# DM3370_OV9782_3-4.net
KiCad netlist of a schematic drawn in Altium Designer
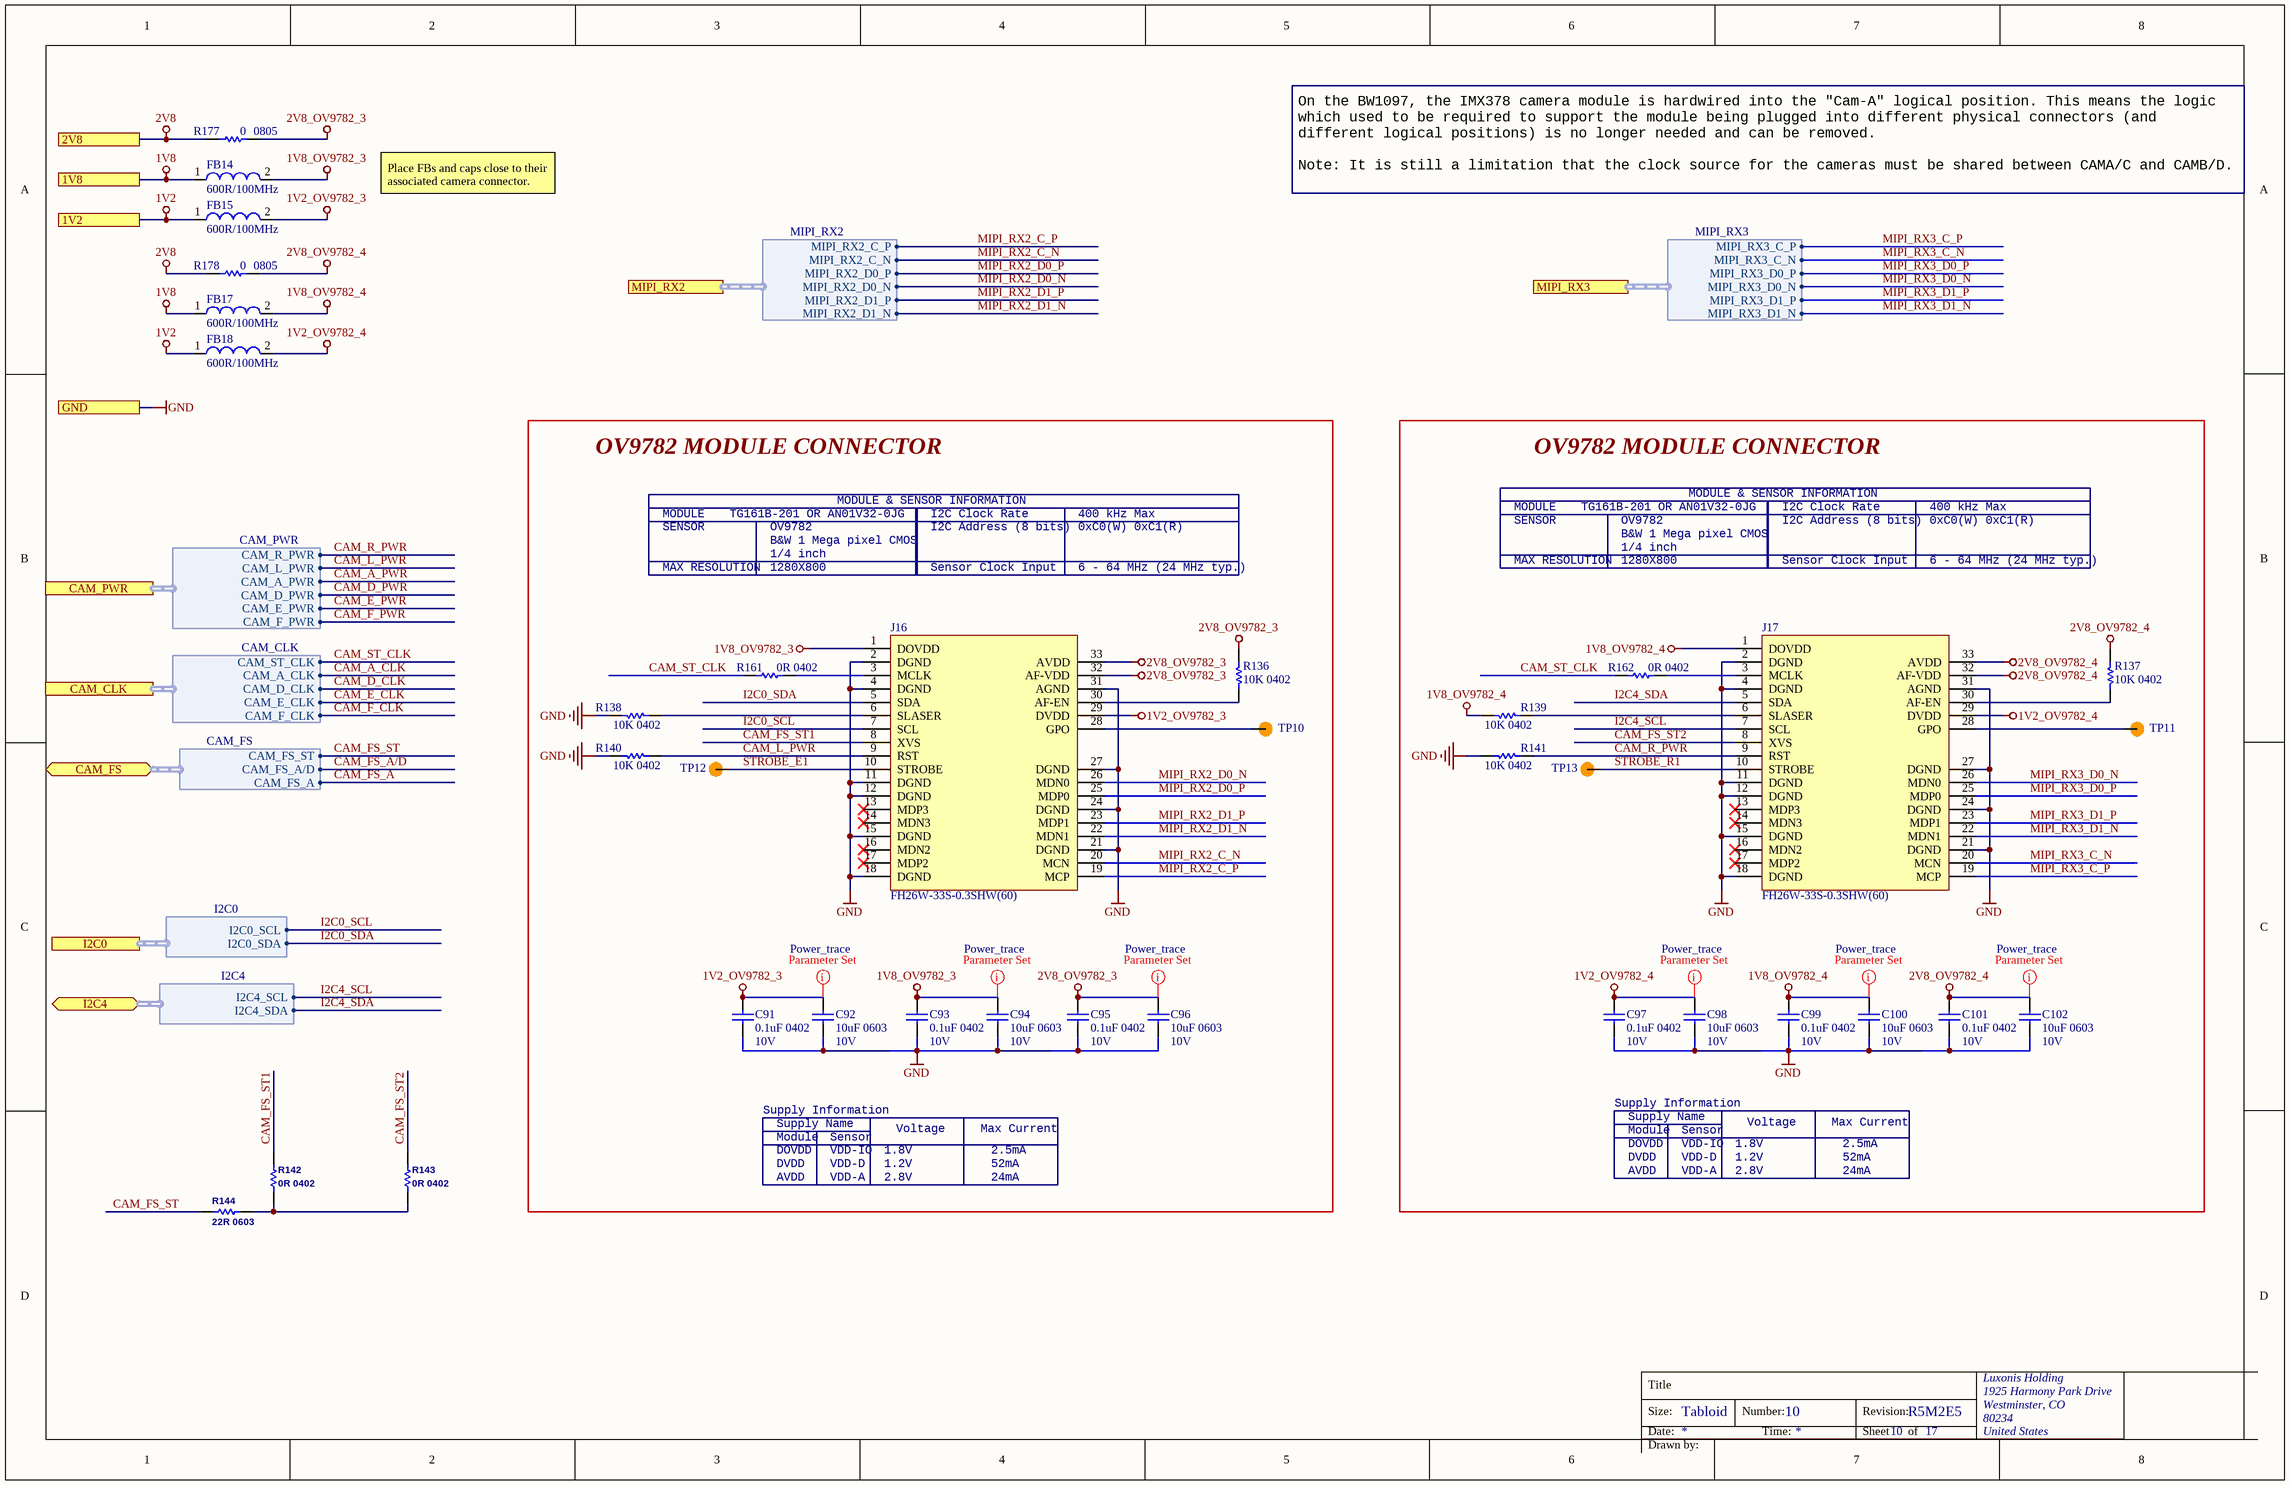
[diagram p0: DM3370_OV9782_3-4.SchDoc]

(export (version "E")
  (design (tool "Eeschema 10.0.6"))
  (components
    (comp (ref "C91")
      (value "0.1uF 0402")
      (footprint "CAP_Altium_Vault_Generic:CAPC0402(1005)70_L")
      (description "CAP CER 0.1UF 10V X7R 0402 5%")
      (fields (field (name "TOLERANCE") "5%") (field (name "VOLTAGE RATING") "10V"))
      (libsource (lib "LuxonisMaster") (part "GRM155R71A104JA01D"))
    )
    (comp (ref "C92")
      (value "10uF 0603")
      (footprint "CAP_Altium_Vault_Generic:CAPC0603(1608)100_L")
      (description "CAP CER 10UF 10V X5R 0603 20%")
      (fields (field (name "TOLERANCE") "20%") (field (name "VOLTAGE RATING") "10V"))
      (libsource (lib "LuxonisMaster") (part "GRM188R61A106ME69D"))
    )
    (comp (ref "C93")
      (value "0.1uF 0402")
      (footprint "CAP_Altium_Vault_Generic:CAPC0402(1005)70_L")
      (description "CAP CER 0.1UF 10V X7R 0402 5%")
      (fields (field (name "TOLERANCE") "5%") (field (name "VOLTAGE RATING") "10V"))
      (libsource (lib "LuxonisMaster") (part "GRM155R71A104JA01D"))
    )
    (comp (ref "C94")
      (value "10uF 0603")
      (footprint "CAP_Altium_Vault_Generic:CAPC0603(1608)100_L")
      (description "CAP CER 10UF 10V X5R 0603 20%")
      (fields (field (name "TOLERANCE") "20%") (field (name "VOLTAGE RATING") "10V"))
      (libsource (lib "LuxonisMaster") (part "GRM188R61A106ME69D"))
    )
    (comp (ref "C95")
      (value "0.1uF 0402")
      (footprint "CAP_Altium_Vault_Generic:CAPC0402(1005)70_L")
      (description "CAP CER 0.1UF 10V X7R 0402 5%")
      (fields (field (name "TOLERANCE") "5%") (field (name "VOLTAGE RATING") "10V"))
      (libsource (lib "LuxonisMaster") (part "GRM155R71A104JA01D"))
    )
    (comp (ref "C96")
      (value "10uF 0603")
      (footprint "CAP_Altium_Vault_Generic:CAPC0603(1608)100_L")
      (description "CAP CER 10UF 10V X5R 0603 20%")
      (fields (field (name "TOLERANCE") "20%") (field (name "VOLTAGE RATING") "10V"))
      (libsource (lib "LuxonisMaster") (part "GRM188R61A106ME69D"))
    )
    (comp (ref "C97")
      (value "0.1uF 0402")
      (footprint "CAP_Altium_Vault_Generic:CAPC0402(1005)70_L")
      (description "CAP CER 0.1UF 10V X7R 0402 5%")
      (fields (field (name "TOLERANCE") "5%") (field (name "VOLTAGE RATING") "10V"))
      (libsource (lib "LuxonisMaster") (part "GRM155R71A104JA01D"))
    )
    (comp (ref "C98")
      (value "10uF 0603")
      (footprint "CAP_Altium_Vault_Generic:CAPC0603(1608)100_L")
      (description "CAP CER 10UF 10V X5R 0603 20%")
      (fields (field (name "TOLERANCE") "20%") (field (name "VOLTAGE RATING") "10V"))
      (libsource (lib "LuxonisMaster") (part "GRM188R61A106ME69D"))
    )
    (comp (ref "C99")
      (value "0.1uF 0402")
      (footprint "CAP_Altium_Vault_Generic:CAPC0402(1005)70_L")
      (description "CAP CER 0.1UF 10V X7R 0402 5%")
      (fields (field (name "TOLERANCE") "5%") (field (name "VOLTAGE RATING") "10V"))
      (libsource (lib "LuxonisMaster") (part "GRM155R71A104JA01D"))
    )
    (comp (ref "C100")
      (value "10uF 0603")
      (footprint "CAP_Altium_Vault_Generic:CAPC0603(1608)100_L")
      (description "CAP CER 10UF 10V X5R 0603 20%")
      (fields (field (name "TOLERANCE") "20%") (field (name "VOLTAGE RATING") "10V"))
      (libsource (lib "LuxonisMaster") (part "GRM188R61A106ME69D"))
    )
    (comp (ref "C101")
      (value "0.1uF 0402")
      (footprint "CAP_Altium_Vault_Generic:CAPC0402(1005)70_L")
      (description "CAP CER 0.1UF 10V X7R 0402 5%")
      (fields (field (name "TOLERANCE") "5%") (field (name "VOLTAGE RATING") "10V"))
      (libsource (lib "LuxonisMaster") (part "GRM155R71A104JA01D"))
    )
    (comp (ref "C102")
      (value "10uF 0603")
      (footprint "CAP_Altium_Vault_Generic:CAPC0603(1608)100_L")
      (description "CAP CER 10UF 10V X5R 0603 20%")
      (fields (field (name "TOLERANCE") "20%") (field (name "VOLTAGE RATING") "10V"))
      (libsource (lib "LuxonisMaster") (part "GRM188R61A106ME69D"))
    )
    (comp (ref "FB14")
      (value "600R/100MHz")
      (footprint "LuxonisMaster:2508056017Y2")
      (description "FERRITE BEAD, 0.1OHM, 2A, 0805, 600R/100MHz")
      (fields (field (name "TOLERANCE") "25%"))
      (libsource (lib "LuxonisMaster") (part "2508056017Y2"))
    )
    (comp (ref "FB15")
      (value "600R/100MHz")
      (footprint "LuxonisMaster:2508056017Y2")
      (description "FERRITE BEAD, 0.1OHM, 2A, 0805, 600R/100MHz")
      (fields (field (name "TOLERANCE") "25%"))
      (libsource (lib "LuxonisMaster") (part "2508056017Y2"))
    )
    (comp (ref "FB17")
      (value "600R/100MHz")
      (footprint "LuxonisMaster:2508056017Y2")
      (description "FERRITE BEAD, 0.1OHM, 2A, 0805, 600R/100MHz")
      (fields (field (name "TOLERANCE") "25%"))
      (libsource (lib "LuxonisMaster") (part "2508056017Y2"))
    )
    (comp (ref "FB18")
      (value "600R/100MHz")
      (footprint "LuxonisMaster:2508056017Y2")
      (description "FERRITE BEAD, 0.1OHM, 2A, 0805, 600R/100MHz")
      (fields (field (name "TOLERANCE") "25%"))
      (libsource (lib "LuxonisMaster") (part "2508056017Y2"))
    )
    (comp (ref "J16")
      (value "FH26W-33S-0.3SHW(60)")
      (footprint "FH26W-33S-0.3SHW(60)")
      (description "FFC/FPC Connector, 33 Contact(s), 1 Row(s), Female, Right Angle, Surface Mount Terminal")
      (libsource (lib "Luxonis LLC") (part "FH26W-33S-0.3SHW(60)"))
    )
    (comp (ref "J17")
      (value "FH26W-33S-0.3SHW(60)")
      (footprint "FH26W-33S-0.3SHW(60)")
      (description "FFC/FPC Connector, 33 Contact(s), 1 Row(s), Female, Right Angle, Surface Mount Terminal")
      (libsource (lib "Luxonis LLC") (part "FH26W-33S-0.3SHW(60)"))
    )
    (comp (ref "R136")
      (value "10K 0402")
      (footprint "RES_Altium_Vault_Generic:RESC0402(1005)_L")
      (fields (field (name "TOLERANCE") "1%"))
      (libsource (lib "LuxonisMaster") (part "RC0402FR-1310KL"))
    )
    (comp (ref "R137")
      (value "10K 0402")
      (footprint "RES_Altium_Vault_Generic:RESC0402(1005)_L")
      (fields (field (name "TOLERANCE") "1%"))
      (libsource (lib "LuxonisMaster") (part "RC0402FR-1310KL"))
    )
    (comp (ref "R138")
      (value "10K 0402")
      (footprint "RES_Altium_Vault_Generic:RESC0402(1005)_L")
      (fields (field (name "TOLERANCE") "1%"))
      (libsource (lib "LuxonisMaster") (part "RC0402FR-1310KL"))
    )
    (comp (ref "R139")
      (value "10K 0402")
      (footprint "RES_Altium_Vault_Generic:RESC0402(1005)_L")
      (fields (field (name "TOLERANCE") "1%"))
      (libsource (lib "LuxonisMaster") (part "RC0402FR-1310KL"))
    )
    (comp (ref "R140")
      (value "10K 0402")
      (footprint "RES_Altium_Vault_Generic:RESC0402(1005)_L")
      (fields (field (name "TOLERANCE") "1%"))
      (libsource (lib "LuxonisMaster") (part "RC0402FR-1310KL"))
    )
    (comp (ref "R141")
      (value "10K 0402")
      (footprint "RES_Altium_Vault_Generic:RESC0402(1005)_L")
      (fields (field (name "TOLERANCE") "1%"))
      (libsource (lib "LuxonisMaster") (part "RC0402FR-1310KL"))
    )
    (comp (ref "R142")
      (value "0R 0402")
      (footprint "RES_Altium_Vault_Generic:RESC0402(1005)_L")
      (description "RES SMD 0 OHM JUMPER 1/16W 0402")
      (fields (field (name "TOLERANCE") "5%"))
      (libsource (lib "LuxonisMaster") (part "CRCW04020000Z0ED"))
    )
    (comp (ref "R143")
      (value "0R 0402")
      (footprint "RES_Altium_Vault_Generic:RESC0402(1005)_L")
      (description "RES SMD 0 OHM JUMPER 1/16W 0402")
      (fields (field (name "TOLERANCE") "5%"))
      (libsource (lib "LuxonisMaster") (part "CRCW04020000Z0ED"))
    )
    (comp (ref "R144")
      (value "22R 0603")
      (footprint "RESC0603(1608)_L")
      (description "RES SMD 22 OHM 1% 1/10W 0603")
      (fields (field (name "TOLERANCE") "1%"))
      (libsource (lib "LuxonisMaster") (part "RC0603FR-0722RL"))
    )
    (comp (ref "R161")
      (value "0R 0402")
      (footprint "RES_Altium_Vault_Generic:RESC0402(1005)_L")
      (description "RES SMD 0 OHM JUMPER 1/16W 0402")
      (fields (field (name "TOLERANCE") "5%"))
      (libsource (lib "LuxonisMaster") (part "CRCW04020000Z0ED"))
    )
    (comp (ref "R162")
      (value "0R 0402")
      (footprint "RES_Altium_Vault_Generic:RESC0402(1005)_L")
      (description "RES SMD 0 OHM JUMPER 1/16W 0402")
      (fields (field (name "TOLERANCE") "5%"))
      (libsource (lib "LuxonisMaster") (part "CRCW04020000Z0ED"))
    )
    (comp (ref "R177")
      (value "0")
      (footprint "RESC0805(2012)_L")
      (description "RES SMD 0 OHM 1% 1/8W 0805")
      (fields (field (name "CASE/PACKAGE") "0805") (field (name "Comment") "CRCW08050000Z0EA"))
      (libsource (lib "Luxonis LLC") (part "Default resistor symbol"))
    )
    (comp (ref "R178")
      (value "0")
      (footprint "RESC0805(2012)_L")
      (description "RES SMD 0 OHM 1% 1/8W 0805")
      (fields (field (name "CASE/PACKAGE") "0805") (field (name "Comment") "CRCW08050000Z0EA"))
      (libsource (lib "Luxonis LLC") (part "Default resistor symbol"))
    )
    (comp (ref "TP10")
      (value "TP100_200_NS")
      (footprint "LuxonisMaster:TP100_200_NS")
      (libsource (lib "LuxonisMaster") (part "TEST_POINT"))
    )
    (comp (ref "TP11")
      (value "TP100_200_NS")
      (footprint "LuxonisMaster:TP100_200_NS")
      (libsource (lib "LuxonisMaster") (part "TEST_POINT"))
    )
    (comp (ref "TP12")
      (value "TP100_200_NS")
      (footprint "LuxonisMaster:TP100_200_NS")
      (libsource (lib "LuxonisMaster") (part "TEST_POINT"))
    )
    (comp (ref "TP13")
      (value "TP100_200_NS")
      (footprint "LuxonisMaster:TP100_200_NS")
      (libsource (lib "LuxonisMaster") (part "TEST_POINT"))
    )
  )
  (nets
    (net (code "16") (name "/CAM_FS_ST") (class "Default")
      (node (ref "R144") (pin "2") (pinfunction "2_2") (pintype "passive"))
    )
    (net (code "17") (name "/CAM_FS_ST1") (class "Default")
      (node (ref "J16") (pin "8") (pinfunction "XVS_8") (pintype "passive"))
      (node (ref "R142") (pin "2") (pinfunction "2_2") (pintype "passive"))
    )
    (net (code "18") (name "/CAM_FS_ST2") (class "Default")
      (node (ref "J17") (pin "8") (pinfunction "XVS_8") (pintype "passive"))
      (node (ref "R143") (pin "2") (pinfunction "2_2") (pintype "passive"))
    )
    (net (code "21") (name "/CAM_L_PWR") (class "Default")
      (node (ref "J16") (pin "9") (pinfunction "RST_9") (pintype "passive"))
      (node (ref "R140") (pin "1") (pinfunction "1_1") (pintype "passive"))
    )
    (net (code "22") (name "/CAM_R_PWR") (class "Default")
      (node (ref "J17") (pin "9") (pinfunction "RST_9") (pintype "passive"))
      (node (ref "R141") (pin "1") (pinfunction "1_1") (pintype "passive"))
    )
    (net (code "23") (name "/CAM_ST_CLK") (class "Default")
      (node (ref "R161") (pin "1") (pinfunction "1_1") (pintype "passive"))
      (node (ref "R162") (pin "1") (pinfunction "1_1") (pintype "passive"))
    )
    (net (code "24") (name "/I2C0_SCL") (class "Default")
      (node (ref "J16") (pin "7") (pinfunction "SCL_7") (pintype "passive"))
    )
    (net (code "25") (name "/I2C0_SDA") (class "Default")
      (node (ref "J16") (pin "5") (pinfunction "SDA_5") (pintype "passive"))
    )
    (net (code "26") (name "/I2C4_SCL") (class "Default")
      (node (ref "J17") (pin "7") (pinfunction "SCL_7") (pintype "passive"))
    )
    (net (code "27") (name "/I2C4_SDA") (class "Default")
      (node (ref "J17") (pin "5") (pinfunction "SDA_5") (pintype "passive"))
    )
    (net (code "28") (name "/MIPI_RX2_C_N") (class "Default")
      (node (ref "J16") (pin "20") (pinfunction "MCN_20") (pintype "passive"))
    )
    (net (code "29") (name "/MIPI_RX2_C_P") (class "Default")
      (node (ref "J16") (pin "19") (pinfunction "MCP_19") (pintype "passive"))
    )
    (net (code "30") (name "/MIPI_RX2_D0_N") (class "Default")
      (node (ref "J16") (pin "26") (pinfunction "MDN0_26") (pintype "passive"))
    )
    (net (code "31") (name "/MIPI_RX2_D0_P") (class "Default")
      (node (ref "J16") (pin "25") (pinfunction "MDP0_25") (pintype "passive"))
    )
    (net (code "32") (name "/MIPI_RX2_D1_N") (class "Default")
      (node (ref "J16") (pin "22") (pinfunction "MDN1_22") (pintype "passive"))
    )
    (net (code "33") (name "/MIPI_RX2_D1_P") (class "Default")
      (node (ref "J16") (pin "23") (pinfunction "MDP1_23") (pintype "passive"))
    )
    (net (code "34") (name "/MIPI_RX3_C_N") (class "Default")
      (node (ref "J17") (pin "20") (pinfunction "MCN_20") (pintype "passive"))
    )
    (net (code "35") (name "/MIPI_RX3_C_P") (class "Default")
      (node (ref "J17") (pin "19") (pinfunction "MCP_19") (pintype "passive"))
    )
    (net (code "36") (name "/MIPI_RX3_D0_N") (class "Default")
      (node (ref "J17") (pin "26") (pinfunction "MDN0_26") (pintype "passive"))
    )
    (net (code "37") (name "/MIPI_RX3_D0_P") (class "Default")
      (node (ref "J17") (pin "25") (pinfunction "MDP0_25") (pintype "passive"))
    )
    (net (code "38") (name "/MIPI_RX3_D1_N") (class "Default")
      (node (ref "J17") (pin "22") (pinfunction "MDN1_22") (pintype "passive"))
    )
    (net (code "39") (name "/MIPI_RX3_D1_P") (class "Default")
      (node (ref "J17") (pin "23") (pinfunction "MDP1_23") (pintype "passive"))
    )
    (net (code "40") (name "/STROBE_E1") (class "Default")
      (node (ref "J16") (pin "10") (pinfunction "STROBE_10") (pintype "passive"))
      (node (ref "TP12") (pin "1") (pintype "passive"))
    )
    (net (code "41") (name "/STROBE_R1") (class "Default")
      (node (ref "J17") (pin "10") (pinfunction "STROBE_10") (pintype "passive"))
      (node (ref "TP13") (pin "1") (pintype "passive"))
    )
    (net (code "49") (name "1V2") (class "Default")
      (node (ref "FB15") (pin "1") (pinfunction "1_1") (pintype "passive"))
      (node (ref "FB18") (pin "1") (pinfunction "1_1") (pintype "passive"))
    )
    (net (code "50") (name "1V2_OV9782_3") (class "Default")
      (node (ref "C91") (pin "2") (pinfunction "2_2") (pintype "passive"))
      (node (ref "C92") (pin "2") (pinfunction "2_2") (pintype "passive"))
      (node (ref "FB15") (pin "2") (pinfunction "2_2") (pintype "passive"))
      (node (ref "J16") (pin "29") (pinfunction "DVDD_29") (pintype "passive"))
    )
    (net (code "51") (name "1V2_OV9782_4") (class "Default")
      (node (ref "C97") (pin "2") (pinfunction "2_2") (pintype "passive"))
      (node (ref "C98") (pin "2") (pinfunction "2_2") (pintype "passive"))
      (node (ref "FB18") (pin "2") (pinfunction "2_2") (pintype "passive"))
      (node (ref "J17") (pin "29") (pinfunction "DVDD_29") (pintype "passive"))
    )
    (net (code "52") (name "1V8") (class "Default")
      (node (ref "FB14") (pin "1") (pinfunction "1_1") (pintype "passive"))
      (node (ref "FB17") (pin "1") (pinfunction "1_1") (pintype "passive"))
    )
    (net (code "53") (name "1V8_OV9782_3") (class "Default")
      (node (ref "C93") (pin "2") (pinfunction "2_2") (pintype "passive"))
      (node (ref "C94") (pin "2") (pinfunction "2_2") (pintype "passive"))
      (node (ref "FB14") (pin "2") (pinfunction "2_2") (pintype "passive"))
      (node (ref "J16") (pin "1") (pinfunction "DOVDD_1") (pintype "passive"))
    )
    (net (code "54") (name "1V8_OV9782_4") (class "Default")
      (node (ref "C100") (pin "2") (pinfunction "2_2") (pintype "passive"))
      (node (ref "C99") (pin "2") (pinfunction "2_2") (pintype "passive"))
      (node (ref "FB17") (pin "2") (pinfunction "2_2") (pintype "passive"))
      (node (ref "J17") (pin "1") (pinfunction "DOVDD_1") (pintype "passive"))
      (node (ref "R139") (pin "2") (pinfunction "2_2") (pintype "passive"))
    )
    (net (code "55") (name "2V8") (class "Default")
      (node (ref "R177") (pin "1") (pinfunction "1_1") (pintype "passive"))
      (node (ref "R178") (pin "1") (pinfunction "1_1") (pintype "passive"))
    )
    (net (code "56") (name "2V8_OV9782_3") (class "Default")
      (node (ref "C95") (pin "2") (pinfunction "2_2") (pintype "passive"))
      (node (ref "C96") (pin "2") (pinfunction "2_2") (pintype "passive"))
      (node (ref "J16") (pin "32") (pinfunction "AF-VDD_32") (pintype "passive"))
      (node (ref "J16") (pin "33") (pinfunction "AVDD_33") (pintype "passive"))
      (node (ref "R136") (pin "1") (pinfunction "1_1") (pintype "passive"))
      (node (ref "R177") (pin "2") (pinfunction "2_2") (pintype "passive"))
    )
    (net (code "57") (name "2V8_OV9782_4") (class "Default")
      (node (ref "C101") (pin "2") (pinfunction "2_2") (pintype "passive"))
      (node (ref "C102") (pin "2") (pinfunction "2_2") (pintype "passive"))
      (node (ref "J17") (pin "32") (pinfunction "AF-VDD_32") (pintype "passive"))
      (node (ref "J17") (pin "33") (pinfunction "AVDD_33") (pintype "passive"))
      (node (ref "R137") (pin "1") (pinfunction "1_1") (pintype "passive"))
      (node (ref "R178") (pin "2") (pinfunction "2_2") (pintype "passive"))
    )
    (net (code "58") (name "GND") (class "Default")
      (node (ref "C100") (pin "1") (pinfunction "1_1") (pintype "passive"))
      (node (ref "C101") (pin "1") (pinfunction "1_1") (pintype "passive"))
      (node (ref "C102") (pin "1") (pinfunction "1_1") (pintype "passive"))
      (node (ref "C91") (pin "1") (pinfunction "1_1") (pintype "passive"))
      (node (ref "C92") (pin "1") (pinfunction "1_1") (pintype "passive"))
      (node (ref "C93") (pin "1") (pinfunction "1_1") (pintype "passive"))
      (node (ref "C94") (pin "1") (pinfunction "1_1") (pintype "passive"))
      (node (ref "C95") (pin "1") (pinfunction "1_1") (pintype "passive"))
      (node (ref "C96") (pin "1") (pinfunction "1_1") (pintype "passive"))
      (node (ref "C97") (pin "1") (pinfunction "1_1") (pintype "passive"))
      (node (ref "C98") (pin "1") (pinfunction "1_1") (pintype "passive"))
      (node (ref "C99") (pin "1") (pinfunction "1_1") (pintype "passive"))
      (node (ref "J16") (pin "11") (pinfunction "DGND_11") (pintype "passive"))
      (node (ref "J16") (pin "12") (pinfunction "DGND_12") (pintype "passive"))
      (node (ref "J16") (pin "15") (pinfunction "DGND_15") (pintype "passive"))
      (node (ref "J16") (pin "18") (pinfunction "DGND_18") (pintype "passive"))
      (node (ref "J16") (pin "2") (pinfunction "DGND_2") (pintype "passive"))
      (node (ref "J16") (pin "21") (pinfunction "DGND_21") (pintype "passive"))
      (node (ref "J16") (pin "24") (pinfunction "DGND_24") (pintype "passive"))
      (node (ref "J16") (pin "27") (pinfunction "DGND_27") (pintype "passive"))
      (node (ref "J16") (pin "31") (pinfunction "AGND_31") (pintype "passive"))
      (node (ref "J16") (pin "4") (pinfunction "DGND_4") (pintype "passive"))
      (node (ref "J17") (pin "11") (pinfunction "DGND_11") (pintype "passive"))
      (node (ref "J17") (pin "12") (pinfunction "DGND_12") (pintype "passive"))
      (node (ref "J17") (pin "15") (pinfunction "DGND_15") (pintype "passive"))
      (node (ref "J17") (pin "18") (pinfunction "DGND_18") (pintype "passive"))
      (node (ref "J17") (pin "2") (pinfunction "DGND_2") (pintype "passive"))
      (node (ref "J17") (pin "21") (pinfunction "DGND_21") (pintype "passive"))
      (node (ref "J17") (pin "24") (pinfunction "DGND_24") (pintype "passive"))
      (node (ref "J17") (pin "27") (pinfunction "DGND_27") (pintype "passive"))
      (node (ref "J17") (pin "31") (pinfunction "AGND_31") (pintype "passive"))
      (node (ref "J17") (pin "4") (pinfunction "DGND_4") (pintype "passive"))
      (node (ref "R138") (pin "2") (pinfunction "2_2") (pintype "passive"))
      (node (ref "R140") (pin "2") (pinfunction "2_2") (pintype "passive"))
      (node (ref "R141") (pin "2") (pinfunction "2_2") (pintype "passive"))
    )
    (net (code "59") (name "Net-(J16-AF-EN)") (class "Default")
      (node (ref "J16") (pin "30") (pinfunction "AF-EN_30") (pintype "passive"))
      (node (ref "R136") (pin "2") (pinfunction "2_2") (pintype "passive"))
    )
    (net (code "60") (name "Net-(J16-GPO)") (class "Default")
      (node (ref "J16") (pin "28") (pinfunction "GPO_28") (pintype "passive"))
      (node (ref "TP10") (pin "1") (pintype "passive"))
    )
    (net (code "61") (name "Net-(J16-MCLK)") (class "Default")
      (node (ref "J16") (pin "3") (pinfunction "MCLK_3") (pintype "passive"))
      (node (ref "R161") (pin "2") (pinfunction "2_2") (pintype "passive"))
    )
    (net (code "62") (name "Net-(J16-SLASER)") (class "Default")
      (node (ref "J16") (pin "6") (pinfunction "SLASER_6") (pintype "passive"))
      (node (ref "R138") (pin "1") (pinfunction "1_1") (pintype "passive"))
    )
    (net (code "63") (name "Net-(J17-AF-EN)") (class "Default")
      (node (ref "J17") (pin "30") (pinfunction "AF-EN_30") (pintype "passive"))
      (node (ref "R137") (pin "2") (pinfunction "2_2") (pintype "passive"))
    )
    (net (code "64") (name "Net-(J17-GPO)") (class "Default")
      (node (ref "J17") (pin "28") (pinfunction "GPO_28") (pintype "passive"))
      (node (ref "TP11") (pin "1") (pintype "passive"))
    )
    (net (code "65") (name "Net-(J17-MCLK)") (class "Default")
      (node (ref "J17") (pin "3") (pinfunction "MCLK_3") (pintype "passive"))
      (node (ref "R162") (pin "2") (pinfunction "2_2") (pintype "passive"))
    )
    (net (code "66") (name "Net-(J17-SLASER)") (class "Default")
      (node (ref "J17") (pin "6") (pinfunction "SLASER_6") (pintype "passive"))
      (node (ref "R139") (pin "1") (pinfunction "1_1") (pintype "passive"))
    )
    (net (code "67") (name "Net-(R142-Pad1)") (class "Default")
      (node (ref "R142") (pin "1") (pinfunction "1_1") (pintype "passive"))
      (node (ref "R143") (pin "1") (pinfunction "1_1") (pintype "passive"))
      (node (ref "R144") (pin "1") (pinfunction "1_1") (pintype "passive"))
    )
    (net (code "68") (name "unconnected-(J16-MDN2-Pad16)") (class "Default")
      (node (ref "J16") (pin "16") (pinfunction "MDN2_16") (pintype "passive+no_connect"))
    )
    (net (code "69") (name "unconnected-(J16-MDN3-Pad14)") (class "Default")
      (node (ref "J16") (pin "14") (pinfunction "MDN3_14") (pintype "passive+no_connect"))
    )
    (net (code "70") (name "unconnected-(J16-MDP2-Pad17)") (class "Default")
      (node (ref "J16") (pin "17") (pinfunction "MDP2_17") (pintype "passive+no_connect"))
    )
    (net (code "71") (name "unconnected-(J16-MDP3-Pad13)") (class "Default")
      (node (ref "J16") (pin "13") (pinfunction "MDP3_13") (pintype "passive+no_connect"))
    )
    (net (code "72") (name "unconnected-(J17-MDN2-Pad16)") (class "Default")
      (node (ref "J17") (pin "16") (pinfunction "MDN2_16") (pintype "passive+no_connect"))
    )
    (net (code "73") (name "unconnected-(J17-MDN3-Pad14)") (class "Default")
      (node (ref "J17") (pin "14") (pinfunction "MDN3_14") (pintype "passive+no_connect"))
    )
    (net (code "74") (name "unconnected-(J17-MDP2-Pad17)") (class "Default")
      (node (ref "J17") (pin "17") (pinfunction "MDP2_17") (pintype "passive+no_connect"))
    )
    (net (code "75") (name "unconnected-(J17-MDP3-Pad13)") (class "Default")
      (node (ref "J17") (pin "13") (pinfunction "MDP3_13") (pintype "passive+no_connect"))
    )
  )
)
